# VCOWaveyRadar.net
KiCad netlist of a schematic drawn in Altium Designer
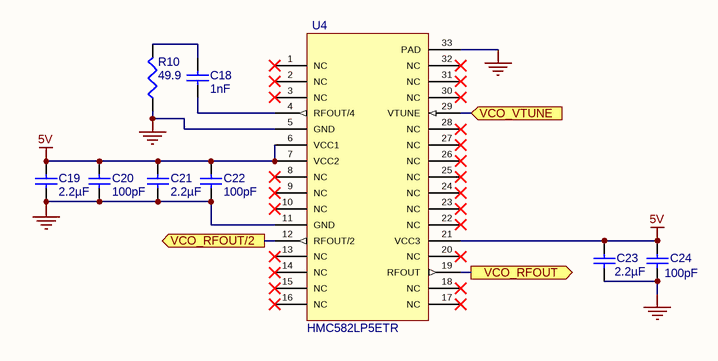
[diagram p0: VCOWaveyRadar.SchDoc]

(export (version "E")
  (design (tool "Eeschema 10.0.6"))
  (components
    (comp (ref "C18")
      (value "1nF")
      (footprint "CAPC0402(1005)33_L")
      (description "Chip Capacitor, 1nF +/-20%, 50V, 0402, Thickness 0.33 mm")
      (fields (field (name "TOLERANCE") "10%") (field (name "Comment") "Capacitor 1nF +/-20% 50V 0402"))
      (libsource (lib "University of South Florida") (part "CAP-NP-2"))
    )
    (comp (ref "C19")
      (value "2.2µF")
      (footprint "CAPC0402(1005)60_L")
      (description "Chip Capacitor, 2,2µF +/-20%, 10V, 0402, Thickness 0.6 mm")
      (fields (field (name "TOLERANCE") "10%") (field (name "Comment") "Capacitor 2,2µF +/-20% 10V 0402"))
      (libsource (lib "University of South Florida") (part "CAP-NP-2"))
    )
    (comp (ref "C20")
      (value "100pF")
      (footprint "CAPC1005X56X25LL10T15")
      (fields (field (name "Comment") "04023A101JAT2A"))
      (libsource (lib "University of South Florida") (part "CAP-NP-2"))
    )
    (comp (ref "C21")
      (value "2.2µF")
      (footprint "CAPC0402(1005)60_L")
      (description "Chip Capacitor, 2,2µF +/-20%, 10V, 0402, Thickness 0.6 mm")
      (fields (field (name "TOLERANCE") "10%") (field (name "Comment") "Capacitor 2,2µF +/-20% 10V 0402"))
      (libsource (lib "University of South Florida") (part "CAP-NP-2"))
    )
    (comp (ref "C22")
      (value "100pF")
      (footprint "CAPC1005X56X25LL10T15")
      (fields (field (name "Comment") "04023A101JAT2A"))
      (libsource (lib "University of South Florida") (part "CAP-NP-2"))
    )
    (comp (ref "C23")
      (value "2.2µF")
      (footprint "CAPC0402(1005)60_L")
      (description "Chip Capacitor, 2,2µF +/-20%, 10V, 0402, Thickness 0.6 mm")
      (fields (field (name "TOLERANCE") "10%") (field (name "Comment") "Capacitor 2,2µF +/-20% 10V 0402"))
      (libsource (lib "University of South Florida") (part "CAP-NP-2"))
    )
    (comp (ref "C24")
      (value "100pF")
      (footprint "CAPC1005X56X25LL10T15")
      (fields (field (name "Comment") "04023A101JAT2A"))
      (libsource (lib "University of South Florida") (part "CAP-NP-2"))
    )
    (comp (ref "R10")
      (value "49.9")
      (footprint "RESC1005X40X25LL10T10")
      (description "RESISTOR, 49R9, 0.063W, 1%, 0402")
      (fields (field (name "Comment") "MC00625W0402149R9"))
      (libsource (lib "University of South Florida") (part "ResistorSymbol"))
    )
    (comp (ref "U4")
      (value "HMC582LP5ETR")
      (footprint "HCP-32-1")
      (description "Voltage Controlled Oscillator 11100MHz to 12400MHz 32-Pin QFN T/R")
      (libsource (lib "University of South Florida") (part "HMC582"))
    )
  )
  (nets
    (net (code "1") (name "/VCO_RFOUT") (class "Default")
      (node (ref "U4") (pin "19") (pinfunction "RFOUT_19") (pintype "output"))
    )
    (net (code "2") (name "/VCO_RFOUT{slash}2") (class "Default")
      (node (ref "U4") (pin "12") (pinfunction "RFOUT/2_12") (pintype "output"))
    )
    (net (code "3") (name "/VCO_VTUNE") (class "Default")
      (node (ref "U4") (pin "29") (pinfunction "VTUNE_29") (pintype "input"))
    )
    (net (code "4") (name "5V") (class "Default")
      (node (ref "C19") (pin "1") (pinfunction "1_1") (pintype "passive"))
      (node (ref "C20") (pin "2") (pinfunction "2_2") (pintype "passive"))
      (node (ref "C21") (pin "1") (pinfunction "1_1") (pintype "passive"))
      (node (ref "C22") (pin "2") (pinfunction "2_2") (pintype "passive"))
      (node (ref "C23") (pin "2") (pinfunction "2_2") (pintype "passive"))
      (node (ref "C24") (pin "1") (pinfunction "1_1") (pintype "passive"))
      (node (ref "U4") (pin "21") (pinfunction "VCC3_21") (pintype "power_in"))
      (node (ref "U4") (pin "6") (pinfunction "VCC1_6") (pintype "power_in"))
      (node (ref "U4") (pin "7") (pinfunction "VCC2_7") (pintype "power_in"))
    )
    (net (code "5") (name "GND") (class "Default")
      (node (ref "C19") (pin "2") (pinfunction "2_2") (pintype "passive"))
      (node (ref "C20") (pin "1") (pinfunction "1_1") (pintype "passive"))
      (node (ref "C21") (pin "2") (pinfunction "2_2") (pintype "passive"))
      (node (ref "C22") (pin "1") (pinfunction "1_1") (pintype "passive"))
      (node (ref "C23") (pin "1") (pinfunction "1_1") (pintype "passive"))
      (node (ref "C24") (pin "2") (pinfunction "2_2") (pintype "passive"))
      (node (ref "R10") (pin "1") (pinfunction "1_1") (pintype "passive"))
      (node (ref "U4") (pin "11") (pinfunction "GND_11") (pintype "power_in"))
      (node (ref "U4") (pin "33") (pinfunction "PAD_33") (pintype "power_in"))
      (node (ref "U4") (pin "5") (pinfunction "GND_5") (pintype "power_in"))
    )
    (net (code "6") (name "Net-(C18-Pad2)") (class "Default")
      (node (ref "C18") (pin "2") (pinfunction "2_2") (pintype "passive"))
      (node (ref "R10") (pin "2") (pinfunction "2_2") (pintype "passive"))
    )
    (net (code "7") (name "Net-(U4-RFOUT{slash}4)") (class "Default")
      (node (ref "C18") (pin "1") (pinfunction "1_1") (pintype "passive"))
      (node (ref "U4") (pin "4") (pinfunction "RFOUT/4_4") (pintype "output"))
    )
    (net (code "8") (name "unconnected-(U4-NC-Pad1)") (class "Default")
      (node (ref "U4") (pin "1") (pinfunction "NC_1") (pintype "passive+no_connect"))
    )
    (net (code "9") (name "unconnected-(U4-NC-Pad2)") (class "Default")
      (node (ref "U4") (pin "2") (pinfunction "NC_2") (pintype "passive+no_connect"))
    )
    (net (code "10") (name "unconnected-(U4-NC-Pad3)") (class "Default")
      (node (ref "U4") (pin "3") (pinfunction "NC_3") (pintype "passive+no_connect"))
    )
    (net (code "11") (name "unconnected-(U4-NC-Pad8)") (class "Default")
      (node (ref "U4") (pin "8") (pinfunction "NC_8") (pintype "passive+no_connect"))
    )
    (net (code "12") (name "unconnected-(U4-NC-Pad9)") (class "Default")
      (node (ref "U4") (pin "9") (pinfunction "NC_9") (pintype "passive+no_connect"))
    )
    (net (code "13") (name "unconnected-(U4-NC-Pad10)") (class "Default")
      (node (ref "U4") (pin "10") (pinfunction "NC_10") (pintype "passive+no_connect"))
    )
    (net (code "14") (name "unconnected-(U4-NC-Pad13)") (class "Default")
      (node (ref "U4") (pin "13") (pinfunction "NC_13") (pintype "passive+no_connect"))
    )
    (net (code "15") (name "unconnected-(U4-NC-Pad14)") (class "Default")
      (node (ref "U4") (pin "14") (pinfunction "NC_14") (pintype "passive+no_connect"))
    )
    (net (code "16") (name "unconnected-(U4-NC-Pad15)") (class "Default")
      (node (ref "U4") (pin "15") (pinfunction "NC_15") (pintype "passive+no_connect"))
    )
    (net (code "17") (name "unconnected-(U4-NC-Pad16)") (class "Default")
      (node (ref "U4") (pin "16") (pinfunction "NC_16") (pintype "passive+no_connect"))
    )
    (net (code "18") (name "unconnected-(U4-NC-Pad17)") (class "Default")
      (node (ref "U4") (pin "17") (pinfunction "NC_17") (pintype "passive+no_connect"))
    )
    (net (code "19") (name "unconnected-(U4-NC-Pad18)") (class "Default")
      (node (ref "U4") (pin "18") (pinfunction "NC_18") (pintype "passive+no_connect"))
    )
    (net (code "20") (name "unconnected-(U4-NC-Pad20)") (class "Default")
      (node (ref "U4") (pin "20") (pinfunction "NC_20") (pintype "passive+no_connect"))
    )
    (net (code "21") (name "unconnected-(U4-NC-Pad22)") (class "Default")
      (node (ref "U4") (pin "22") (pinfunction "NC_22") (pintype "passive+no_connect"))
    )
    (net (code "22") (name "unconnected-(U4-NC-Pad23)") (class "Default")
      (node (ref "U4") (pin "23") (pinfunction "NC_23") (pintype "passive+no_connect"))
    )
    (net (code "23") (name "unconnected-(U4-NC-Pad24)") (class "Default")
      (node (ref "U4") (pin "24") (pinfunction "NC_24") (pintype "passive+no_connect"))
    )
    (net (code "24") (name "unconnected-(U4-NC-Pad25)") (class "Default")
      (node (ref "U4") (pin "25") (pinfunction "NC_25") (pintype "passive+no_connect"))
    )
    (net (code "25") (name "unconnected-(U4-NC-Pad26)") (class "Default")
      (node (ref "U4") (pin "26") (pinfunction "NC_26") (pintype "passive+no_connect"))
    )
    (net (code "26") (name "unconnected-(U4-NC-Pad27)") (class "Default")
      (node (ref "U4") (pin "27") (pinfunction "NC_27") (pintype "passive+no_connect"))
    )
    (net (code "27") (name "unconnected-(U4-NC-Pad28)") (class "Default")
      (node (ref "U4") (pin "28") (pinfunction "NC_28") (pintype "passive+no_connect"))
    )
    (net (code "28") (name "unconnected-(U4-NC-Pad30)") (class "Default")
      (node (ref "U4") (pin "30") (pinfunction "NC_30") (pintype "passive+no_connect"))
    )
    (net (code "29") (name "unconnected-(U4-NC-Pad31)") (class "Default")
      (node (ref "U4") (pin "31") (pinfunction "NC_31") (pintype "passive+no_connect"))
    )
    (net (code "30") (name "unconnected-(U4-NC-Pad32)") (class "Default")
      (node (ref "U4") (pin "32") (pinfunction "NC_32") (pintype "passive+no_connect"))
    )
  )
)
